# PERIPHERALS.net
KiCad netlist of a schematic drawn in Altium Designer
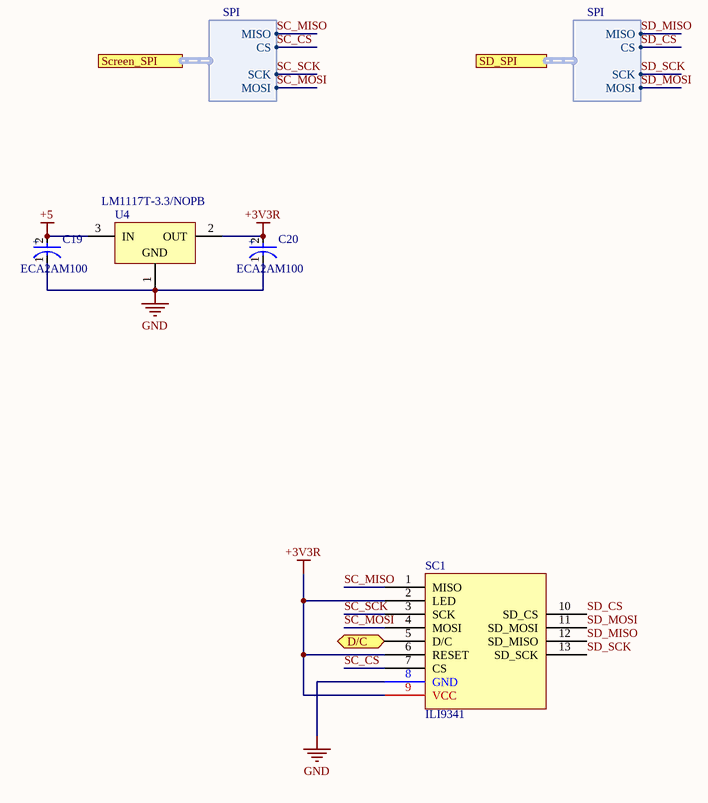
[diagram p0: PERIPHERALS.SchDoc]

(export (version "E")
  (design (tool "Eeschema 10.0.6"))
  (components
    (comp (ref "C19")
      (value "ECA2AM100")
      (footprint "FP-RAD-TH-D_5_0_5-L_11_1-MFG")
      (description "Aluminum Electrolytic Capacitors (Radial Lead Type) 10uF ±20% 100V")
      (fields (field (name "VOLTAGE") "100V") (field (name "TOLERANCE") "20%"))
      (libsource (lib "Components - 12.08.25 - 13.17") (part "CMP-05427-000869-1"))
    )
    (comp (ref "C20")
      (value "ECA2AM100")
      (footprint "FP-RAD-TH-D_5_0_5-L_11_1-MFG")
      (description "Aluminum Electrolytic Capacitors (Radial Lead Type) 10uF ±20% 100V")
      (fields (field (name "VOLTAGE") "100V") (field (name "TOLERANCE") "20%"))
      (libsource (lib "Components - 12.08.25 - 13.17") (part "CMP-05427-000869-1"))
    )
    (comp (ref "SC1") (value "ILI9341") (footprint "ILI9341") (libsource (lib "ILI9341") (part "ILI9341")))
    (comp (ref "U4")
      (value "LM1117T-3.3/NOPB")
      (footprint "NDE0003A")
      (description "800mA Low-Dropout Linear Regulator, 3-pin TO-220, Pb-Free")
      (fields (field (name "MANUFACTURER") "Texas Instruments"))
      (libsource (lib "Components - 12.08.25 - 13.16") (part "CMP-0062-02494-3"))
    )
  )
  (nets
    (net (code "2") (name "+3V3R") (class "Default")
      (node (ref "C20") (pin "2") (pinfunction "A_2") (pintype "passive"))
      (node (ref "SC1") (pin "2") (pinfunction "LED_2") (pintype "passive"))
      (node (ref "SC1") (pin "6") (pinfunction "RESET_6") (pintype "passive"))
      (node (ref "SC1") (pin "9") (pinfunction "VCC_9") (pintype "power_in"))
      (node (ref "U4") (pin "2") (pinfunction "OUT_2") (pintype "power_in"))
    )
    (net (code "3") (name "+5") (class "Default")
      (node (ref "C19") (pin "2") (pinfunction "A_2") (pintype "passive"))
      (node (ref "U4") (pin "3") (pinfunction "IN_3") (pintype "power_in"))
    )
    (net (code "4") (name "/D{slash}C") (class "Default")
      (node (ref "SC1") (pin "5") (pinfunction "D/C_5") (pintype "passive"))
    )
    (net (code "5") (name "/SC_CS") (class "Default")
      (node (ref "SC1") (pin "7") (pinfunction "CS_7") (pintype "passive"))
    )
    (net (code "6") (name "/SC_MISO") (class "Default")
      (node (ref "SC1") (pin "1") (pinfunction "MISO_1") (pintype "passive"))
    )
    (net (code "7") (name "/SC_MOSI") (class "Default")
      (node (ref "SC1") (pin "4") (pinfunction "MOSI_4") (pintype "passive"))
    )
    (net (code "8") (name "/SC_SCK") (class "Default")
      (node (ref "SC1") (pin "3") (pinfunction "SCK_3") (pintype "passive"))
    )
    (net (code "9") (name "/SD_CS") (class "Default")
      (node (ref "SC1") (pin "10") (pinfunction "SD_CS_10") (pintype "passive"))
    )
    (net (code "10") (name "/SD_MISO") (class "Default")
      (node (ref "SC1") (pin "12") (pinfunction "SD_MISO_12") (pintype "passive"))
    )
    (net (code "11") (name "/SD_MOSI") (class "Default")
      (node (ref "SC1") (pin "11") (pinfunction "SD_MOSI_11") (pintype "passive"))
    )
    (net (code "12") (name "/SD_SCK") (class "Default")
      (node (ref "SC1") (pin "13") (pinfunction "SD_SCK_13") (pintype "passive"))
    )
    (net (code "14") (name "GND") (class "Default")
      (node (ref "C19") (pin "1") (pinfunction "C_1") (pintype "passive"))
      (node (ref "C20") (pin "1") (pinfunction "C_1") (pintype "passive"))
      (node (ref "SC1") (pin "8") (pinfunction "GND_8") (pintype "power_in"))
      (node (ref "U4") (pin "1") (pinfunction "GND_1") (pintype "power_in"))
    )
  )
)
